# NMEA2000-DS1820.net
KiCad netlist of a schematic drawn in EAGLE
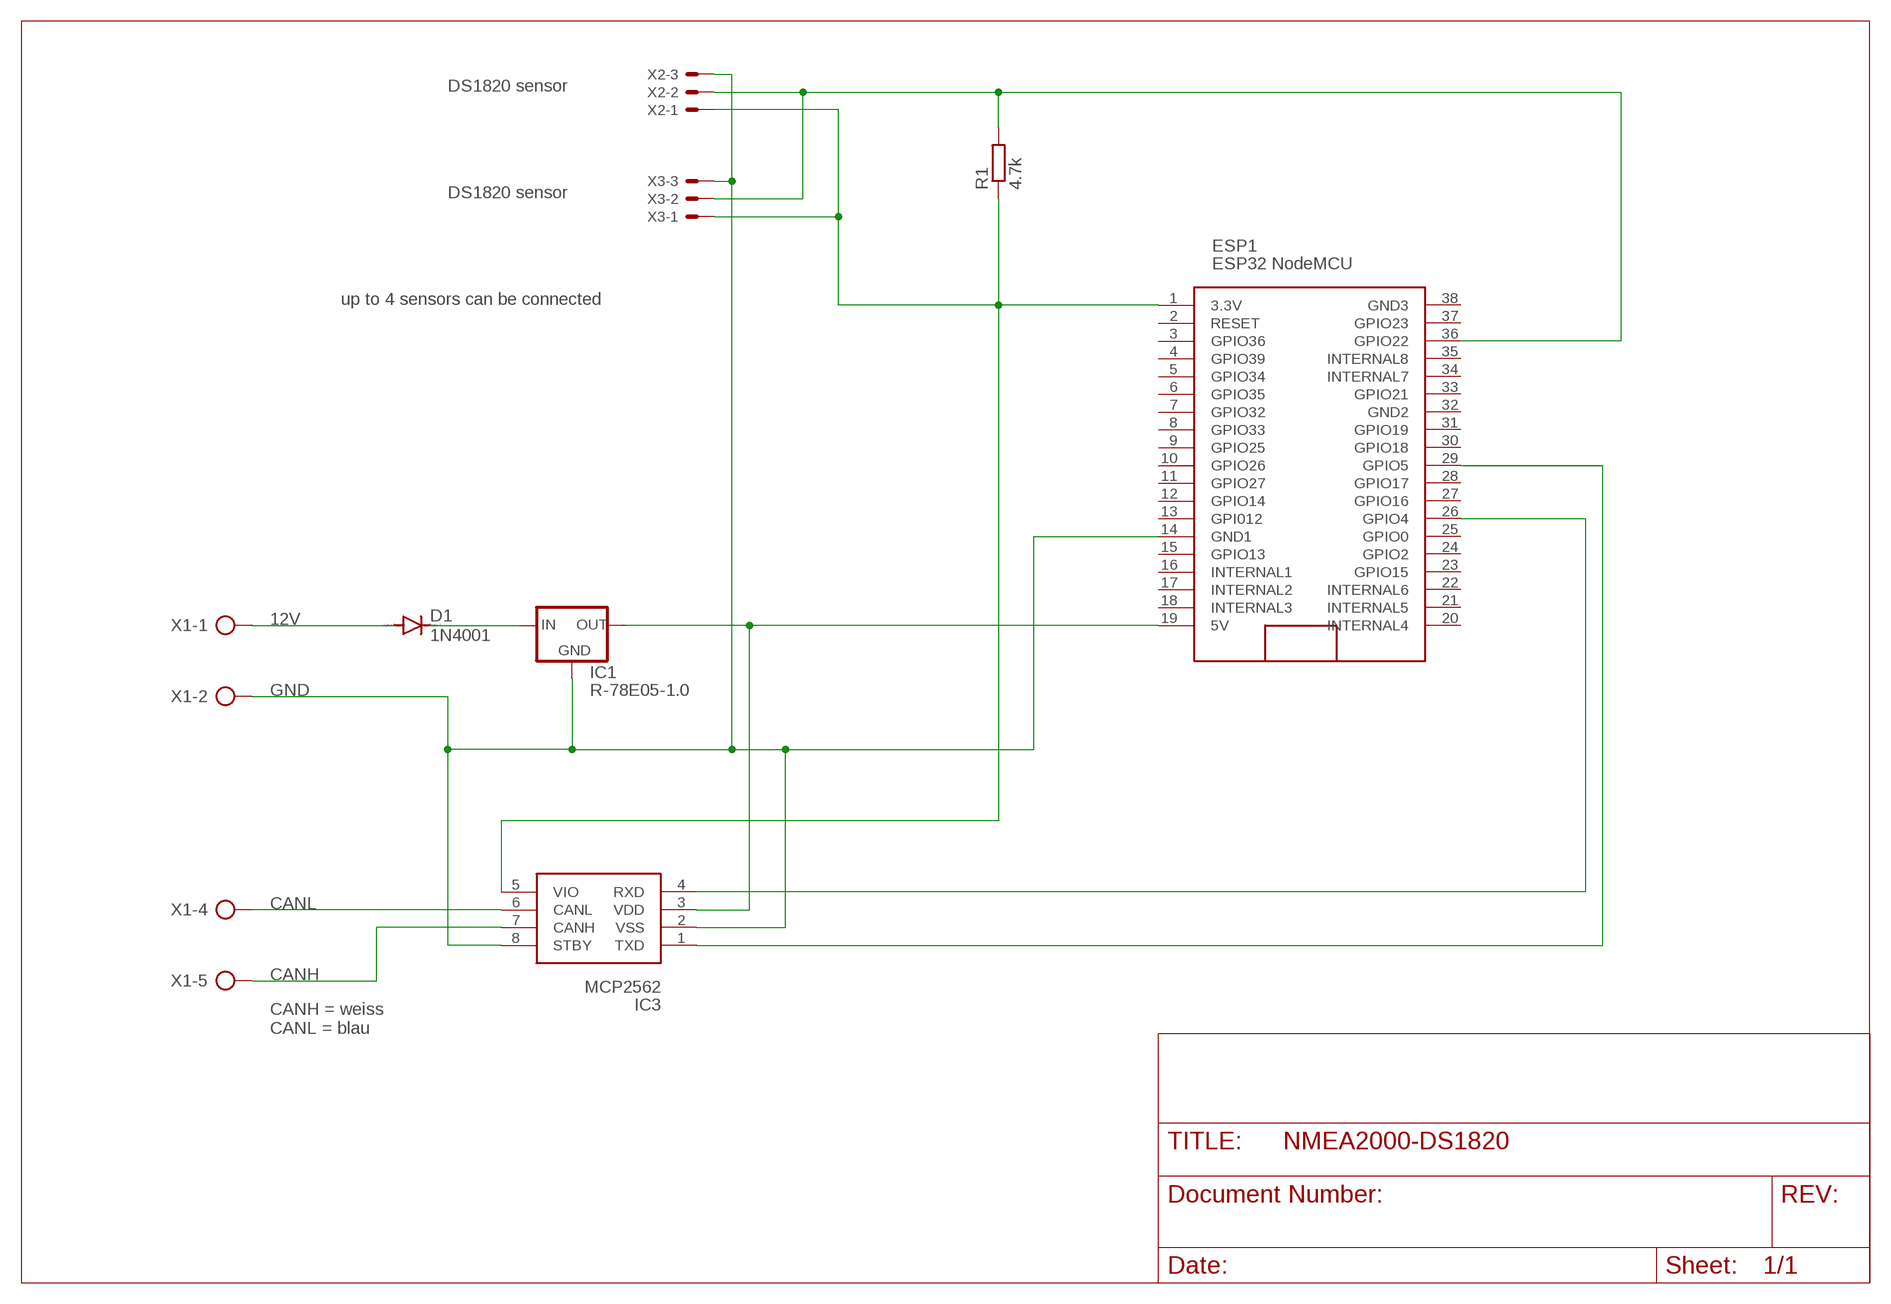
[diagram p0: schematic, sheet 1]

(export (version "E")
  (design (tool "Eeschema 10.0.6"))
  (components
    (comp (ref "D1")
      (value "1N4001")
      (footprint "eagle-import:DO41-10")
      (libsource (lib "eagle-import") (part "1N4004"))
    )
    (comp (ref "ESP1")
      (value "ESP32 NodeMCU")
      (footprint "eagle-import:ESP32_NODEMCU")
      (libsource (lib "eagle-import") (part "ESP32-NODEMCU"))
    )
    (comp (ref "IC1")
      (value "R-78E05-1.0")
      (footprint "eagle-import:78XXS")
      (libsource (lib "eagle-import") (part "78XXS"))
    )
    (comp (ref "IC3")
      (value "MCP2562")
      (footprint "eagle-import:DIL08")
      (libsource (lib "eagle-import") (part "MCP2562"))
    )
    (comp (ref "R1")
      (value "4.7k")
      (footprint "eagle-import:0204_7")
      (libsource (lib "eagle-import") (part "R-EU_0204/7"))
    )
    (comp (ref "X1")
      (value "AK500/5")
      (footprint "eagle-import:AK500_5")
      (libsource (lib "eagle-import") (part "AK500/5"))
    )
    (comp (ref "X2")
      (value "22-23-2031")
      (footprint "eagle-import:22-23-2031")
      (fields (field (name "MF") "MOLEX"))
      (libsource (lib "eagle-import") (part "22-23-2031"))
    )
    (comp (ref "X3")
      (value "22-23-2031")
      (footprint "eagle-import:22-23-2031")
      (fields (field (name "MF") "MOLEX"))
      (libsource (lib "eagle-import") (part "22-23-2031"))
    )
  )
  (nets
    (net (code "1") (name "/12V") (class "Default")
      (node (ref "D1") (pin "A") (pinfunction "A_A") (pintype "passive"))
      (node (ref "X1") (pin "1") (pinfunction "KL_1") (pintype "passive"))
    )
    (net (code "2") (name "/CANH") (class "Default")
      (node (ref "IC3") (pin "7") (pinfunction "CANH_7") (pintype "bidirectional"))
      (node (ref "X1") (pin "5") (pinfunction "KL_5") (pintype "passive"))
    )
    (net (code "3") (name "/CANL") (class "Default")
      (node (ref "IC3") (pin "6") (pinfunction "CANL_6") (pintype "bidirectional"))
      (node (ref "X1") (pin "4") (pinfunction "KL_4") (pintype "passive"))
    )
    (net (code "4") (name "/GND") (class "Default")
      (node (ref "ESP1") (pin "14") (pinfunction "GND1_14") (pintype "power_in"))
      (node (ref "IC1") (pin "GND") (pinfunction "GND_GND") (pintype "input"))
      (node (ref "IC3") (pin "2") (pinfunction "VSS_2") (pintype "bidirectional"))
      (node (ref "IC3") (pin "8") (pinfunction "STBY_8") (pintype "bidirectional"))
      (node (ref "X1") (pin "2") (pinfunction "KL_2") (pintype "passive"))
      (node (ref "X2") (pin "3") (pinfunction "S_3") (pintype "passive"))
      (node (ref "X3") (pin "3") (pinfunction "S_3") (pintype "passive"))
    )
    (net (code "5") (name "/GND2") (class "Default")
      (node (ref "ESP1") (pin "32") (pinfunction "GND2_32") (pintype "power_in"))
    )
    (net (code "6") (name "/GND3") (class "Default")
      (node (ref "ESP1") (pin "38") (pinfunction "GND3_38") (pintype "power_in"))
    )
    (net (code "7") (name "Net-(D1-PadC)") (class "Default")
      (node (ref "D1") (pin "C") (pinfunction "C_C") (pintype "passive"))
      (node (ref "IC1") (pin "IN") (pinfunction "IN_IN") (pintype "input"))
    )
    (net (code "8") (name "Net-(ESP1-3.3V)") (class "Default")
      (node (ref "ESP1") (pin "1") (pinfunction "3.3V_1") (pintype "power_in"))
      (node (ref "IC3") (pin "5") (pinfunction "VIO_5") (pintype "bidirectional"))
      (node (ref "R1") (pin "1") (pinfunction "1_1") (pintype "passive"))
      (node (ref "X2") (pin "1") (pinfunction "S_1") (pintype "passive"))
      (node (ref "X3") (pin "1") (pinfunction "S_1") (pintype "passive"))
    )
    (net (code "9") (name "Net-(ESP1-5V)") (class "Default")
      (node (ref "ESP1") (pin "19") (pinfunction "5V_19") (pintype "power_in"))
      (node (ref "IC1") (pin "OUT") (pinfunction "OUT_OUT") (pintype "passive"))
      (node (ref "IC3") (pin "3") (pinfunction "VDD_3") (pintype "bidirectional"))
    )
    (net (code "10") (name "Net-(ESP1-GPIO4)") (class "Default")
      (node (ref "ESP1") (pin "26") (pinfunction "GPIO4_26") (pintype "bidirectional"))
      (node (ref "IC3") (pin "4") (pinfunction "RXD_4") (pintype "bidirectional"))
    )
    (net (code "11") (name "Net-(ESP1-GPIO5)") (class "Default")
      (node (ref "ESP1") (pin "29") (pinfunction "GPIO5_29") (pintype "bidirectional"))
      (node (ref "IC3") (pin "1") (pinfunction "TXD_1") (pintype "bidirectional"))
    )
    (net (code "12") (name "Net-(ESP1-GPIO22)") (class "Default")
      (node (ref "ESP1") (pin "36") (pinfunction "GPIO22_36") (pintype "bidirectional"))
      (node (ref "R1") (pin "2") (pinfunction "2_2") (pintype "passive"))
      (node (ref "X2") (pin "2") (pinfunction "S_2") (pintype "passive"))
      (node (ref "X3") (pin "2") (pinfunction "S_2") (pintype "passive"))
    )
    (net (code "13") (name "unconnected-(ESP1-GPI012-Pad13)") (class "Default")
      (node (ref "ESP1") (pin "13") (pinfunction "GPI012_13") (pintype "bidirectional"))
    )
    (net (code "14") (name "unconnected-(ESP1-GPIO0-Pad25)") (class "Default")
      (node (ref "ESP1") (pin "25") (pinfunction "GPIO0_25") (pintype "output"))
    )
    (net (code "15") (name "unconnected-(ESP1-GPIO2-Pad24)") (class "Default")
      (node (ref "ESP1") (pin "24") (pinfunction "GPIO2_24") (pintype "bidirectional"))
    )
    (net (code "16") (name "unconnected-(ESP1-GPIO13-Pad15)") (class "Default")
      (node (ref "ESP1") (pin "15") (pinfunction "GPIO13_15") (pintype "bidirectional"))
    )
    (net (code "17") (name "unconnected-(ESP1-GPIO14-Pad12)") (class "Default")
      (node (ref "ESP1") (pin "12") (pinfunction "GPIO14_12") (pintype "bidirectional"))
    )
    (net (code "18") (name "unconnected-(ESP1-GPIO15-Pad23)") (class "Default")
      (node (ref "ESP1") (pin "23") (pinfunction "GPIO15_23") (pintype "bidirectional"))
    )
    (net (code "19") (name "unconnected-(ESP1-GPIO16-Pad27)") (class "Default")
      (node (ref "ESP1") (pin "27") (pinfunction "GPIO16_27") (pintype "bidirectional"))
    )
    (net (code "20") (name "unconnected-(ESP1-GPIO17-Pad28)") (class "Default")
      (node (ref "ESP1") (pin "28") (pinfunction "GPIO17_28") (pintype "bidirectional"))
    )
    (net (code "21") (name "unconnected-(ESP1-GPIO18-Pad30)") (class "Default")
      (node (ref "ESP1") (pin "30") (pinfunction "GPIO18_30") (pintype "bidirectional"))
    )
    (net (code "22") (name "unconnected-(ESP1-GPIO19-Pad31)") (class "Default")
      (node (ref "ESP1") (pin "31") (pinfunction "GPIO19_31") (pintype "bidirectional"))
    )
    (net (code "23") (name "unconnected-(ESP1-GPIO21-Pad33)") (class "Default")
      (node (ref "ESP1") (pin "33") (pinfunction "GPIO21_33") (pintype "bidirectional"))
    )
    (net (code "24") (name "unconnected-(ESP1-GPIO23-Pad37)") (class "Default")
      (node (ref "ESP1") (pin "37") (pinfunction "GPIO23_37") (pintype "bidirectional"))
    )
    (net (code "25") (name "unconnected-(ESP1-GPIO25-Pad9)") (class "Default")
      (node (ref "ESP1") (pin "9") (pinfunction "GPIO25_9") (pintype "bidirectional"))
    )
    (net (code "26") (name "unconnected-(ESP1-GPIO26-Pad10)") (class "Default")
      (node (ref "ESP1") (pin "10") (pinfunction "GPIO26_10") (pintype "bidirectional"))
    )
    (net (code "27") (name "unconnected-(ESP1-GPIO27-Pad11)") (class "Default")
      (node (ref "ESP1") (pin "11") (pinfunction "GPIO27_11") (pintype "bidirectional"))
    )
    (net (code "28") (name "unconnected-(ESP1-GPIO32-Pad7)") (class "Default")
      (node (ref "ESP1") (pin "7") (pinfunction "GPIO32_7") (pintype "bidirectional"))
    )
    (net (code "29") (name "unconnected-(ESP1-GPIO33-Pad8)") (class "Default")
      (node (ref "ESP1") (pin "8") (pinfunction "GPIO33_8") (pintype "bidirectional"))
    )
    (net (code "30") (name "unconnected-(ESP1-GPIO34-Pad5)") (class "Default")
      (node (ref "ESP1") (pin "5") (pinfunction "GPIO34_5") (pintype "input"))
    )
    (net (code "31") (name "unconnected-(ESP1-GPIO35-Pad6)") (class "Default")
      (node (ref "ESP1") (pin "6") (pinfunction "GPIO35_6") (pintype "input"))
    )
    (net (code "32") (name "unconnected-(ESP1-GPIO36-Pad3)") (class "Default")
      (node (ref "ESP1") (pin "3") (pinfunction "GPIO36_3") (pintype "input"))
    )
    (net (code "33") (name "unconnected-(ESP1-GPIO39-Pad4)") (class "Default")
      (node (ref "ESP1") (pin "4") (pinfunction "GPIO39_4") (pintype "input"))
    )
    (net (code "34") (name "unconnected-(ESP1-INTERNAL1-Pad16)") (class "Default")
      (node (ref "ESP1") (pin "16") (pinfunction "INTERNAL1_16") (pintype "no_connect"))
    )
    (net (code "35") (name "unconnected-(ESP1-INTERNAL2-Pad17)") (class "Default")
      (node (ref "ESP1") (pin "17") (pinfunction "INTERNAL2_17") (pintype "no_connect"))
    )
    (net (code "36") (name "unconnected-(ESP1-INTERNAL3-Pad18)") (class "Default")
      (node (ref "ESP1") (pin "18") (pinfunction "INTERNAL3_18") (pintype "no_connect"))
    )
    (net (code "37") (name "unconnected-(ESP1-INTERNAL4-Pad20)") (class "Default")
      (node (ref "ESP1") (pin "20") (pinfunction "INTERNAL4_20") (pintype "no_connect"))
    )
    (net (code "38") (name "unconnected-(ESP1-INTERNAL5-Pad21)") (class "Default")
      (node (ref "ESP1") (pin "21") (pinfunction "INTERNAL5_21") (pintype "no_connect"))
    )
    (net (code "39") (name "unconnected-(ESP1-INTERNAL6-Pad22)") (class "Default")
      (node (ref "ESP1") (pin "22") (pinfunction "INTERNAL6_22") (pintype "no_connect"))
    )
    (net (code "40") (name "unconnected-(ESP1-INTERNAL7-Pad34)") (class "Default")
      (node (ref "ESP1") (pin "34") (pinfunction "INTERNAL7_34") (pintype "no_connect"))
    )
    (net (code "41") (name "unconnected-(ESP1-INTERNAL8-Pad35)") (class "Default")
      (node (ref "ESP1") (pin "35") (pinfunction "INTERNAL8_35") (pintype "no_connect"))
    )
    (net (code "42") (name "unconnected-(ESP1-RESET-Pad2)") (class "Default")
      (node (ref "ESP1") (pin "2") (pinfunction "RESET_2") (pintype "input"))
    )
  )
)
